# RADU-Master-S00-V00.net
KiCad netlist of a schematic drawn in Altium Designer
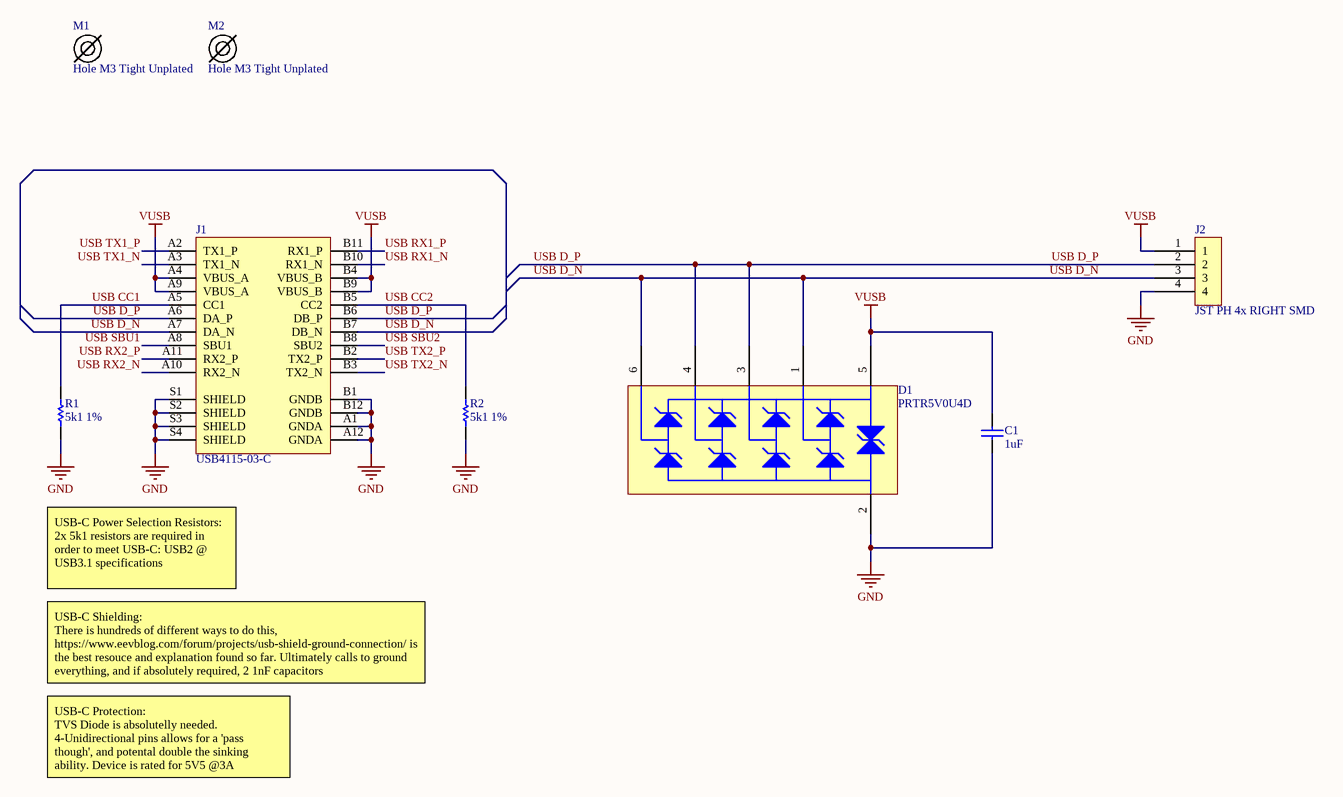
[diagram p0: RADU-Master-S00-V00.SchDoc]

(export (version "E")
  (design (tool "Eeschema 10.0.6"))
  (components
    (comp (ref "C1")
      (value "1uF")
      (footprint "Cap_Ceramic_0603")
      (description "Capacitor, Ceramic, SMD, 1uF, 25V, 5%, X7R, 0603")
      (libsource (lib "StandardCapacitors") (part "1uF 25V 5% X7R 0603"))
    )
    (comp (ref "D1")
      (value "PRTR5V0U4D")
      (footprint "SC-47")
      (description "Clamp Ipp Tvs Diode Surface Mount 6-TSOP")
      (libsource (lib "QUTMS_DiodeLibrary") (part "PRTR5V0U4D"))
    )
    (comp (ref "J1")
      (value "USB4115-03-C")
      (footprint "USB4115-03-C")
      (libsource (lib "QUTMS_USBLibrary") (part "USB4115-03-C"))
    )
    (comp (ref "J2")
      (value "JST PH 4x RIGHT SMD")
      (footprint "JST PH 4x RIGHT SMD")
      (libsource (lib "QUTMS_JST_PH") (part "JST PH 4x RIGHT SMD"))
    )
    (comp (ref "M1")
      (value "Hole M3 Tight Unplated")
      (footprint "M3.2 UNPLATED")
      (description "M3.2 Hole, No Plating")
      (libsource (lib "QUTMS_PCBLibrary") (part "Hole M3 Tight Unplated"))
    )
    (comp (ref "M2")
      (value "Hole M3 Tight Unplated")
      (footprint "M3.2 UNPLATED")
      (description "M3.2 Hole, No Plating")
      (libsource (lib "QUTMS_PCBLibrary") (part "Hole M3 Tight Unplated"))
    )
    (comp (ref "R1")
      (value "5k1 1%")
      (footprint "Res_ThinFilm_0603")
      (description "Resistor, SMD, 5k1, 0.1W, 1%, 0603")
      (libsource (lib "StandardResistors") (part "5k1 1% 0603"))
    )
    (comp (ref "R2")
      (value "5k1 1%")
      (footprint "Res_ThinFilm_0603")
      (description "Resistor, SMD, 5k1, 0.1W, 1%, 0603")
      (libsource (lib "StandardResistors") (part "5k1 1% 0603"))
    )
  )
  (nets
    (net (code "1") (name "/USB CC1") (class "Default")
      (node (ref "J1") (pin "A5") (pinfunction "CC1_A5") (pintype "passive"))
      (node (ref "R1") (pin "2") (pinfunction "2_2") (pintype "passive"))
    )
    (net (code "2") (name "/USB CC2") (class "Default")
      (node (ref "J1") (pin "B5") (pinfunction "CC2_B5") (pintype "passive"))
      (node (ref "R2") (pin "2") (pinfunction "2_2") (pintype "passive"))
    )
    (net (code "3") (name "/USB D_N") (class "Default")
      (node (ref "D1") (pin "1") (pinfunction "P1_1") (pintype "passive"))
      (node (ref "D1") (pin "6") (pinfunction "P4_6") (pintype "passive"))
      (node (ref "J1") (pin "A7") (pinfunction "DA_N_A7") (pintype "passive"))
      (node (ref "J1") (pin "B7") (pinfunction "DB_N_B7") (pintype "passive"))
      (node (ref "J2") (pin "3") (pinfunction "3_3") (pintype "passive"))
    )
    (net (code "4") (name "/USB D_P") (class "Default")
      (node (ref "D1") (pin "3") (pinfunction "P2_3") (pintype "passive"))
      (node (ref "D1") (pin "4") (pinfunction "P3_4") (pintype "passive"))
      (node (ref "J1") (pin "A6") (pinfunction "DA_P_A6") (pintype "passive"))
      (node (ref "J1") (pin "B6") (pinfunction "DB_P_B6") (pintype "passive"))
      (node (ref "J2") (pin "2") (pinfunction "2_2") (pintype "passive"))
    )
    (net (code "5") (name "/USB RX1_N") (class "Default")
      (node (ref "J1") (pin "B10") (pinfunction "RX1_N_B10") (pintype "passive"))
    )
    (net (code "6") (name "/USB RX1_P") (class "Default")
      (node (ref "J1") (pin "B11") (pinfunction "RX1_P_B11") (pintype "passive"))
    )
    (net (code "7") (name "/USB RX2_N") (class "Default")
      (node (ref "J1") (pin "A10") (pinfunction "RX2_N_A10") (pintype "passive"))
    )
    (net (code "8") (name "/USB RX2_P") (class "Default")
      (node (ref "J1") (pin "A11") (pinfunction "RX2_P_A11") (pintype "passive"))
    )
    (net (code "9") (name "/USB SBU1") (class "Default")
      (node (ref "J1") (pin "A8") (pinfunction "SBU1_A8") (pintype "passive"))
    )
    (net (code "10") (name "/USB SBU2") (class "Default")
      (node (ref "J1") (pin "B8") (pinfunction "SBU2_B8") (pintype "passive"))
    )
    (net (code "11") (name "/USB TX1_N") (class "Default")
      (node (ref "J1") (pin "A3") (pinfunction "TX1_N_A3") (pintype "passive"))
    )
    (net (code "12") (name "/USB TX1_P") (class "Default")
      (node (ref "J1") (pin "A2") (pinfunction "TX1_P_A2") (pintype "passive"))
    )
    (net (code "13") (name "/USB TX2_N") (class "Default")
      (node (ref "J1") (pin "B3") (pinfunction "TX2_N_B3") (pintype "passive"))
    )
    (net (code "14") (name "/USB TX2_P") (class "Default")
      (node (ref "J1") (pin "B2") (pinfunction "TX2_P_B2") (pintype "passive"))
    )
    (net (code "15") (name "GND") (class "Default")
      (node (ref "C1") (pin "1") (pinfunction "1_1") (pintype "passive"))
      (node (ref "D1") (pin "2") (pinfunction "GND_2") (pintype "passive"))
      (node (ref "J1") (pin "A1") (pinfunction "GNDA_A1") (pintype "passive"))
      (node (ref "J1") (pin "A12") (pinfunction "GNDA_A12") (pintype "passive"))
      (node (ref "J1") (pin "B1") (pinfunction "GNDB_B1") (pintype "passive"))
      (node (ref "J1") (pin "B12") (pinfunction "GNDB_B12") (pintype "passive"))
      (node (ref "J1") (pin "S1") (pinfunction "SHIELD_S1") (pintype "power_in"))
      (node (ref "J1") (pin "S2") (pinfunction "SHIELD_S2") (pintype "power_in"))
      (node (ref "J1") (pin "S3") (pinfunction "SHIELD_S3") (pintype "power_in"))
      (node (ref "J1") (pin "S4") (pinfunction "SHIELD_S4") (pintype "power_in"))
      (node (ref "J2") (pin "4") (pinfunction "4_4") (pintype "passive"))
      (node (ref "R1") (pin "1") (pinfunction "1_1") (pintype "passive"))
      (node (ref "R2") (pin "1") (pinfunction "1_1") (pintype "passive"))
    )
    (net (code "16") (name "VUSB") (class "Default")
      (node (ref "C1") (pin "2") (pinfunction "2_2") (pintype "passive"))
      (node (ref "D1") (pin "5") (pinfunction "VCC_5") (pintype "passive"))
      (node (ref "J1") (pin "A4") (pinfunction "VBUS_A_A4") (pintype "passive"))
      (node (ref "J1") (pin "A9") (pinfunction "VBUS_A_A9") (pintype "passive"))
      (node (ref "J1") (pin "B4") (pinfunction "VBUS_B_B4") (pintype "passive"))
      (node (ref "J1") (pin "B9") (pinfunction "VBUS_B_B9") (pintype "passive"))
      (node (ref "J2") (pin "1") (pinfunction "1_1") (pintype "passive"))
    )
  )
)
